# relais-with-led-indicator.net
KiCad netlist of a schematic drawn in EAGLE
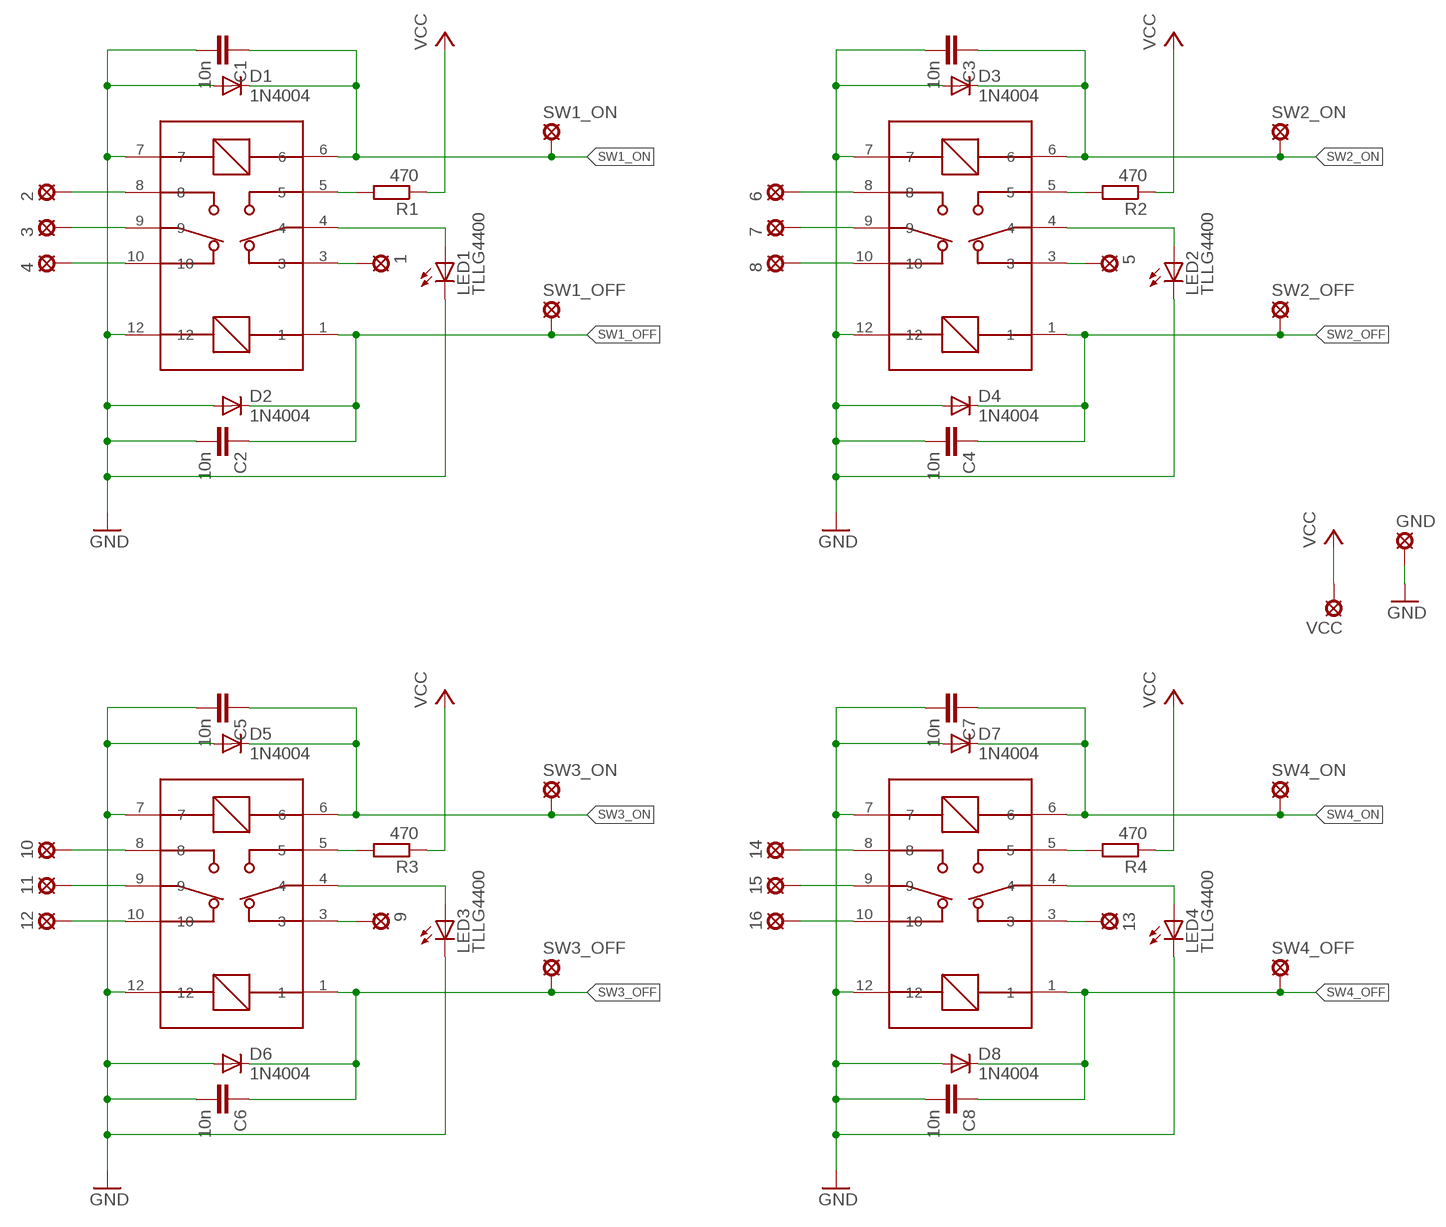
[diagram p0: schematic, sheet 1]

(export (version "E")
  (design (tool "Eeschema 10.0.6"))
  (components
    (comp (ref "1")
      (value "LSP10")
      (footprint "eagle-import:LSP10")
      (libsource (lib "eagle-import") (part "LSP10"))
    )
    (comp (ref "2")
      (value "LSP10")
      (footprint "eagle-import:LSP10")
      (libsource (lib "eagle-import") (part "LSP10"))
    )
    (comp (ref "3")
      (value "LSP10")
      (footprint "eagle-import:LSP10")
      (libsource (lib "eagle-import") (part "LSP10"))
    )
    (comp (ref "4")
      (value "LSP10")
      (footprint "eagle-import:LSP10")
      (libsource (lib "eagle-import") (part "LSP10"))
    )
    (comp (ref "5")
      (value "LSP10")
      (footprint "eagle-import:LSP10")
      (libsource (lib "eagle-import") (part "LSP10"))
    )
    (comp (ref "6")
      (value "LSP10")
      (footprint "eagle-import:LSP10")
      (libsource (lib "eagle-import") (part "LSP10"))
    )
    (comp (ref "7")
      (value "LSP10")
      (footprint "eagle-import:LSP10")
      (libsource (lib "eagle-import") (part "LSP10"))
    )
    (comp (ref "8")
      (value "LSP10")
      (footprint "eagle-import:LSP10")
      (libsource (lib "eagle-import") (part "LSP10"))
    )
    (comp (ref "9")
      (value "LSP10")
      (footprint "eagle-import:LSP10")
      (libsource (lib "eagle-import") (part "LSP10"))
    )
    (comp (ref "10")
      (value "LSP10")
      (footprint "eagle-import:LSP10")
      (libsource (lib "eagle-import") (part "LSP10"))
    )
    (comp (ref "11")
      (value "LSP10")
      (footprint "eagle-import:LSP10")
      (libsource (lib "eagle-import") (part "LSP10"))
    )
    (comp (ref "12")
      (value "LSP10")
      (footprint "eagle-import:LSP10")
      (libsource (lib "eagle-import") (part "LSP10"))
    )
    (comp (ref "13")
      (value "LSP10")
      (footprint "eagle-import:LSP10")
      (libsource (lib "eagle-import") (part "LSP10"))
    )
    (comp (ref "14")
      (value "LSP10")
      (footprint "eagle-import:LSP10")
      (libsource (lib "eagle-import") (part "LSP10"))
    )
    (comp (ref "15")
      (value "LSP10")
      (footprint "eagle-import:LSP10")
      (libsource (lib "eagle-import") (part "LSP10"))
    )
    (comp (ref "16")
      (value "LSP10")
      (footprint "eagle-import:LSP10")
      (libsource (lib "eagle-import") (part "LSP10"))
    )
    (comp (ref "C1")
      (value "10n")
      (footprint "eagle-import:C050-024X044")
      (libsource (lib "eagle-import") (part "C-EU050-024X044"))
    )
    (comp (ref "C2")
      (value "10n")
      (footprint "eagle-import:C050-024X044")
      (libsource (lib "eagle-import") (part "C-EU050-024X044"))
    )
    (comp (ref "C3")
      (value "10n")
      (footprint "eagle-import:C050-024X044")
      (libsource (lib "eagle-import") (part "C-EU050-024X044"))
    )
    (comp (ref "C4")
      (value "10n")
      (footprint "eagle-import:C050-024X044")
      (libsource (lib "eagle-import") (part "C-EU050-024X044"))
    )
    (comp (ref "C5")
      (value "10n")
      (footprint "eagle-import:C050-024X044")
      (libsource (lib "eagle-import") (part "C-EU050-024X044"))
    )
    (comp (ref "C6")
      (value "10n")
      (footprint "eagle-import:C050-024X044")
      (libsource (lib "eagle-import") (part "C-EU050-024X044"))
    )
    (comp (ref "C7")
      (value "10n")
      (footprint "eagle-import:C050-024X044")
      (libsource (lib "eagle-import") (part "C-EU050-024X044"))
    )
    (comp (ref "C8")
      (value "10n")
      (footprint "eagle-import:C050-024X044")
      (libsource (lib "eagle-import") (part "C-EU050-024X044"))
    )
    (comp (ref "D1")
      (value "1N4004")
      (footprint "eagle-import:DO41-10")
      (libsource (lib "eagle-import") (part "1N4004"))
    )
    (comp (ref "D2")
      (value "1N4004")
      (footprint "eagle-import:DO41-10")
      (libsource (lib "eagle-import") (part "1N4004"))
    )
    (comp (ref "D3")
      (value "1N4004")
      (footprint "eagle-import:DO41-10")
      (libsource (lib "eagle-import") (part "1N4004"))
    )
    (comp (ref "D4")
      (value "1N4004")
      (footprint "eagle-import:DO41-10")
      (libsource (lib "eagle-import") (part "1N4004"))
    )
    (comp (ref "D5")
      (value "1N4004")
      (footprint "eagle-import:DO41-10")
      (libsource (lib "eagle-import") (part "1N4004"))
    )
    (comp (ref "D6")
      (value "1N4004")
      (footprint "eagle-import:DO41-10")
      (libsource (lib "eagle-import") (part "1N4004"))
    )
    (comp (ref "D7")
      (value "1N4004")
      (footprint "eagle-import:DO41-10")
      (libsource (lib "eagle-import") (part "1N4004"))
    )
    (comp (ref "D8")
      (value "1N4004")
      (footprint "eagle-import:DO41-10")
      (libsource (lib "eagle-import") (part "1N4004"))
    )
    (comp (ref "GND")
      (value "LSP10")
      (footprint "eagle-import:LSP10")
      (libsource (lib "eagle-import") (part "LSP10"))
    )
    (comp (ref "LED1")
      (value "TLLG4400")
      (footprint "eagle-import:LED3MM")
      (fields (field (name "MF") "VISHAY SEMICONDUCTOR"))
      (libsource (lib "eagle-import") (part "TLLG4400"))
    )
    (comp (ref "LED2")
      (value "TLLG4400")
      (footprint "eagle-import:LED3MM")
      (fields (field (name "MF") "VISHAY SEMICONDUCTOR"))
      (libsource (lib "eagle-import") (part "TLLG4400"))
    )
    (comp (ref "LED3")
      (value "TLLG4400")
      (footprint "eagle-import:LED3MM")
      (fields (field (name "MF") "VISHAY SEMICONDUCTOR"))
      (libsource (lib "eagle-import") (part "TLLG4400"))
    )
    (comp (ref "LED4")
      (value "TLLG4400")
      (footprint "eagle-import:LED3MM")
      (fields (field (name "MF") "VISHAY SEMICONDUCTOR"))
      (libsource (lib "eagle-import") (part "TLLG4400"))
    )
    (comp (ref "R1")
      (value "470")
      (footprint "eagle-import:0204_7")
      (libsource (lib "eagle-import") (part "R0204/7"))
    )
    (comp (ref "R2")
      (value "470")
      (footprint "eagle-import:0204_7")
      (libsource (lib "eagle-import") (part "R0204/7"))
    )
    (comp (ref "R3")
      (value "470")
      (footprint "eagle-import:0204_7")
      (libsource (lib "eagle-import") (part "R0204/7"))
    )
    (comp (ref "R4")
      (value "470")
      (footprint "eagle-import:0204_7")
      (libsource (lib "eagle-import") (part "R0204/7"))
    )
    (comp (ref "RL1")
      (value "BISTABIL-2-COILS")
      (footprint "eagle-import:BISTABILE-2-COILS")
      (libsource (lib "eagle-import") (part "BISTABIL-2-COILS"))
    )
    (comp (ref "RL2")
      (value "BISTABIL-2-COILS")
      (footprint "eagle-import:BISTABILE-2-COILS")
      (libsource (lib "eagle-import") (part "BISTABIL-2-COILS"))
    )
    (comp (ref "RL3")
      (value "BISTABIL-2-COILS")
      (footprint "eagle-import:BISTABILE-2-COILS")
      (libsource (lib "eagle-import") (part "BISTABIL-2-COILS"))
    )
    (comp (ref "RL4")
      (value "BISTABIL-2-COILS")
      (footprint "eagle-import:BISTABILE-2-COILS")
      (libsource (lib "eagle-import") (part "BISTABIL-2-COILS"))
    )
    (comp (ref "SW1_OFF")
      (value "LSP10")
      (footprint "eagle-import:LSP10")
      (libsource (lib "eagle-import") (part "LSP10"))
    )
    (comp (ref "SW1_ON")
      (value "LSP10")
      (footprint "eagle-import:LSP10")
      (libsource (lib "eagle-import") (part "LSP10"))
    )
    (comp (ref "SW2_OFF")
      (value "LSP10")
      (footprint "eagle-import:LSP10")
      (libsource (lib "eagle-import") (part "LSP10"))
    )
    (comp (ref "SW2_ON")
      (value "LSP10")
      (footprint "eagle-import:LSP10")
      (libsource (lib "eagle-import") (part "LSP10"))
    )
    (comp (ref "SW3_OFF")
      (value "LSP10")
      (footprint "eagle-import:LSP10")
      (libsource (lib "eagle-import") (part "LSP10"))
    )
    (comp (ref "SW3_ON")
      (value "LSP10")
      (footprint "eagle-import:LSP10")
      (libsource (lib "eagle-import") (part "LSP10"))
    )
    (comp (ref "SW4_OFF")
      (value "LSP10")
      (footprint "eagle-import:LSP10")
      (libsource (lib "eagle-import") (part "LSP10"))
    )
    (comp (ref "SW4_ON")
      (value "LSP10")
      (footprint "eagle-import:LSP10")
      (libsource (lib "eagle-import") (part "LSP10"))
    )
    (comp (ref "VCC")
      (value "LSP10")
      (footprint "eagle-import:LSP10")
      (libsource (lib "eagle-import") (part "LSP10"))
    )
  )
  (nets
    (net (code "1") (name "GND") (class "Default")
      (node (ref "C1") (pin "2") (pinfunction "2_2") (pintype "passive"))
      (node (ref "C2") (pin "2") (pinfunction "2_2") (pintype "passive"))
      (node (ref "C3") (pin "2") (pinfunction "2_2") (pintype "passive"))
      (node (ref "C4") (pin "2") (pinfunction "2_2") (pintype "passive"))
      (node (ref "C5") (pin "2") (pinfunction "2_2") (pintype "passive"))
      (node (ref "C6") (pin "2") (pinfunction "2_2") (pintype "passive"))
      (node (ref "C7") (pin "2") (pinfunction "2_2") (pintype "passive"))
      (node (ref "C8") (pin "2") (pinfunction "2_2") (pintype "passive"))
      (node (ref "D1") (pin "A") (pinfunction "A_A") (pintype "passive"))
      (node (ref "D2") (pin "A") (pinfunction "A_A") (pintype "passive"))
      (node (ref "D3") (pin "A") (pinfunction "A_A") (pintype "passive"))
      (node (ref "D4") (pin "A") (pinfunction "A_A") (pintype "passive"))
      (node (ref "D5") (pin "A") (pinfunction "A_A") (pintype "passive"))
      (node (ref "D6") (pin "A") (pinfunction "A_A") (pintype "passive"))
      (node (ref "D7") (pin "A") (pinfunction "A_A") (pintype "passive"))
      (node (ref "D8") (pin "A") (pinfunction "A_A") (pintype "passive"))
      (node (ref "GND") (pin "MP") (pinfunction "MP_MP") (pintype "passive"))
      (node (ref "LED1") (pin "K") (pinfunction "C_K") (pintype "passive"))
      (node (ref "LED2") (pin "K") (pinfunction "C_K") (pintype "passive"))
      (node (ref "LED3") (pin "K") (pinfunction "C_K") (pintype "passive"))
      (node (ref "LED4") (pin "K") (pinfunction "C_K") (pintype "passive"))
      (node (ref "RL1") (pin "12") (pinfunction "12_12") (pintype "bidirectional"))
      (node (ref "RL1") (pin "7") (pinfunction "7_7") (pintype "bidirectional"))
      (node (ref "RL2") (pin "12") (pinfunction "12_12") (pintype "bidirectional"))
      (node (ref "RL2") (pin "7") (pinfunction "7_7") (pintype "bidirectional"))
      (node (ref "RL3") (pin "12") (pinfunction "12_12") (pintype "bidirectional"))
      (node (ref "RL3") (pin "7") (pinfunction "7_7") (pintype "bidirectional"))
      (node (ref "RL4") (pin "12") (pinfunction "12_12") (pintype "bidirectional"))
      (node (ref "RL4") (pin "7") (pinfunction "7_7") (pintype "bidirectional"))
    )
    (net (code "2") (name "Net-(1-PadMP)") (class "Default")
      (node (ref "1") (pin "MP") (pinfunction "MP_MP") (pintype "passive"))
      (node (ref "RL1") (pin "3") (pinfunction "3_3") (pintype "bidirectional"))
    )
    (net (code "3") (name "Net-(2-PadMP)") (class "Default")
      (node (ref "2") (pin "MP") (pinfunction "MP_MP") (pintype "passive"))
      (node (ref "RL1") (pin "8") (pinfunction "8_8") (pintype "bidirectional"))
    )
    (net (code "4") (name "Net-(3-PadMP)") (class "Default")
      (node (ref "3") (pin "MP") (pinfunction "MP_MP") (pintype "passive"))
      (node (ref "RL1") (pin "9") (pinfunction "9_9") (pintype "bidirectional"))
    )
    (net (code "5") (name "Net-(4-PadMP)") (class "Default")
      (node (ref "4") (pin "MP") (pinfunction "MP_MP") (pintype "passive"))
      (node (ref "RL1") (pin "10") (pinfunction "10_10") (pintype "bidirectional"))
    )
    (net (code "6") (name "Net-(5-PadMP)") (class "Default")
      (node (ref "5") (pin "MP") (pinfunction "MP_MP") (pintype "passive"))
      (node (ref "RL2") (pin "3") (pinfunction "3_3") (pintype "bidirectional"))
    )
    (net (code "7") (name "Net-(6-PadMP)") (class "Default")
      (node (ref "6") (pin "MP") (pinfunction "MP_MP") (pintype "passive"))
      (node (ref "RL2") (pin "8") (pinfunction "8_8") (pintype "bidirectional"))
    )
    (net (code "8") (name "Net-(7-PadMP)") (class "Default")
      (node (ref "7") (pin "MP") (pinfunction "MP_MP") (pintype "passive"))
      (node (ref "RL2") (pin "9") (pinfunction "9_9") (pintype "bidirectional"))
    )
    (net (code "9") (name "Net-(8-PadMP)") (class "Default")
      (node (ref "8") (pin "MP") (pinfunction "MP_MP") (pintype "passive"))
      (node (ref "RL2") (pin "10") (pinfunction "10_10") (pintype "bidirectional"))
    )
    (net (code "10") (name "Net-(9-PadMP)") (class "Default")
      (node (ref "9") (pin "MP") (pinfunction "MP_MP") (pintype "passive"))
      (node (ref "RL3") (pin "3") (pinfunction "3_3") (pintype "bidirectional"))
    )
    (net (code "11") (name "Net-(10-PadMP)") (class "Default")
      (node (ref "10") (pin "MP") (pinfunction "MP_MP") (pintype "passive"))
      (node (ref "RL3") (pin "8") (pinfunction "8_8") (pintype "bidirectional"))
    )
    (net (code "12") (name "Net-(11-PadMP)") (class "Default")
      (node (ref "11") (pin "MP") (pinfunction "MP_MP") (pintype "passive"))
      (node (ref "RL3") (pin "9") (pinfunction "9_9") (pintype "bidirectional"))
    )
    (net (code "13") (name "Net-(12-PadMP)") (class "Default")
      (node (ref "12") (pin "MP") (pinfunction "MP_MP") (pintype "passive"))
      (node (ref "RL3") (pin "10") (pinfunction "10_10") (pintype "bidirectional"))
    )
    (net (code "14") (name "Net-(13-PadMP)") (class "Default")
      (node (ref "13") (pin "MP") (pinfunction "MP_MP") (pintype "passive"))
      (node (ref "RL4") (pin "3") (pinfunction "3_3") (pintype "bidirectional"))
    )
    (net (code "15") (name "Net-(14-PadMP)") (class "Default")
      (node (ref "14") (pin "MP") (pinfunction "MP_MP") (pintype "passive"))
      (node (ref "RL4") (pin "8") (pinfunction "8_8") (pintype "bidirectional"))
    )
    (net (code "16") (name "Net-(15-PadMP)") (class "Default")
      (node (ref "15") (pin "MP") (pinfunction "MP_MP") (pintype "passive"))
      (node (ref "RL4") (pin "9") (pinfunction "9_9") (pintype "bidirectional"))
    )
    (net (code "17") (name "Net-(16-PadMP)") (class "Default")
      (node (ref "16") (pin "MP") (pinfunction "MP_MP") (pintype "passive"))
      (node (ref "RL4") (pin "10") (pinfunction "10_10") (pintype "bidirectional"))
    )
    (net (code "18") (name "Net-(LED1-PadA)") (class "Default")
      (node (ref "LED1") (pin "A") (pinfunction "A_A") (pintype "passive"))
      (node (ref "RL1") (pin "4") (pinfunction "4_4") (pintype "bidirectional"))
    )
    (net (code "19") (name "Net-(LED2-PadA)") (class "Default")
      (node (ref "LED2") (pin "A") (pinfunction "A_A") (pintype "passive"))
      (node (ref "RL2") (pin "4") (pinfunction "4_4") (pintype "bidirectional"))
    )
    (net (code "20") (name "Net-(LED3-PadA)") (class "Default")
      (node (ref "LED3") (pin "A") (pinfunction "A_A") (pintype "passive"))
      (node (ref "RL3") (pin "4") (pinfunction "4_4") (pintype "bidirectional"))
    )
    (net (code "21") (name "Net-(LED4-PadA)") (class "Default")
      (node (ref "LED4") (pin "A") (pinfunction "A_A") (pintype "passive"))
      (node (ref "RL4") (pin "4") (pinfunction "4_4") (pintype "bidirectional"))
    )
    (net (code "22") (name "Net-(R1-Pad2)") (class "Default")
      (node (ref "R1") (pin "2") (pinfunction "2_2") (pintype "passive"))
      (node (ref "RL1") (pin "5") (pinfunction "5_5") (pintype "bidirectional"))
    )
    (net (code "23") (name "Net-(R2-Pad2)") (class "Default")
      (node (ref "R2") (pin "2") (pinfunction "2_2") (pintype "passive"))
      (node (ref "RL2") (pin "5") (pinfunction "5_5") (pintype "bidirectional"))
    )
    (net (code "24") (name "Net-(R3-Pad2)") (class "Default")
      (node (ref "R3") (pin "2") (pinfunction "2_2") (pintype "passive"))
      (node (ref "RL3") (pin "5") (pinfunction "5_5") (pintype "bidirectional"))
    )
    (net (code "25") (name "Net-(R4-Pad2)") (class "Default")
      (node (ref "R4") (pin "2") (pinfunction "2_2") (pintype "passive"))
      (node (ref "RL4") (pin "5") (pinfunction "5_5") (pintype "bidirectional"))
    )
    (net (code "26") (name "SW1_OFF") (class "Default")
      (node (ref "C2") (pin "1") (pinfunction "1_1") (pintype "passive"))
      (node (ref "D2") (pin "C") (pinfunction "C_C") (pintype "passive"))
      (node (ref "RL1") (pin "1") (pinfunction "1_1") (pintype "bidirectional"))
      (node (ref "SW1_OFF") (pin "MP") (pinfunction "MP_MP") (pintype "passive"))
    )
    (net (code "27") (name "SW1_ON") (class "Default")
      (node (ref "C1") (pin "1") (pinfunction "1_1") (pintype "passive"))
      (node (ref "D1") (pin "C") (pinfunction "C_C") (pintype "passive"))
      (node (ref "RL1") (pin "6") (pinfunction "6_6") (pintype "bidirectional"))
      (node (ref "SW1_ON") (pin "MP") (pinfunction "MP_MP") (pintype "passive"))
    )
    (net (code "28") (name "SW2_OFF") (class "Default")
      (node (ref "C4") (pin "1") (pinfunction "1_1") (pintype "passive"))
      (node (ref "D4") (pin "C") (pinfunction "C_C") (pintype "passive"))
      (node (ref "RL2") (pin "1") (pinfunction "1_1") (pintype "bidirectional"))
      (node (ref "SW2_OFF") (pin "MP") (pinfunction "MP_MP") (pintype "passive"))
    )
    (net (code "29") (name "SW2_ON") (class "Default")
      (node (ref "C3") (pin "1") (pinfunction "1_1") (pintype "passive"))
      (node (ref "D3") (pin "C") (pinfunction "C_C") (pintype "passive"))
      (node (ref "RL2") (pin "6") (pinfunction "6_6") (pintype "bidirectional"))
      (node (ref "SW2_ON") (pin "MP") (pinfunction "MP_MP") (pintype "passive"))
    )
    (net (code "30") (name "SW3_OFF") (class "Default")
      (node (ref "C6") (pin "1") (pinfunction "1_1") (pintype "passive"))
      (node (ref "D6") (pin "C") (pinfunction "C_C") (pintype "passive"))
      (node (ref "RL3") (pin "1") (pinfunction "1_1") (pintype "bidirectional"))
      (node (ref "SW3_OFF") (pin "MP") (pinfunction "MP_MP") (pintype "passive"))
    )
    (net (code "31") (name "SW3_ON") (class "Default")
      (node (ref "C5") (pin "1") (pinfunction "1_1") (pintype "passive"))
      (node (ref "D5") (pin "C") (pinfunction "C_C") (pintype "passive"))
      (node (ref "RL3") (pin "6") (pinfunction "6_6") (pintype "bidirectional"))
      (node (ref "SW3_ON") (pin "MP") (pinfunction "MP_MP") (pintype "passive"))
    )
    (net (code "32") (name "SW4_OFF") (class "Default")
      (node (ref "C8") (pin "1") (pinfunction "1_1") (pintype "passive"))
      (node (ref "D8") (pin "C") (pinfunction "C_C") (pintype "passive"))
      (node (ref "RL4") (pin "1") (pinfunction "1_1") (pintype "bidirectional"))
      (node (ref "SW4_OFF") (pin "MP") (pinfunction "MP_MP") (pintype "passive"))
    )
    (net (code "33") (name "SW4_ON") (class "Default")
      (node (ref "C7") (pin "1") (pinfunction "1_1") (pintype "passive"))
      (node (ref "D7") (pin "C") (pinfunction "C_C") (pintype "passive"))
      (node (ref "RL4") (pin "6") (pinfunction "6_6") (pintype "bidirectional"))
      (node (ref "SW4_ON") (pin "MP") (pinfunction "MP_MP") (pintype "passive"))
    )
    (net (code "34") (name "VCC") (class "Default")
      (node (ref "R1") (pin "1") (pinfunction "1_1") (pintype "passive"))
      (node (ref "R2") (pin "1") (pinfunction "1_1") (pintype "passive"))
      (node (ref "R3") (pin "1") (pinfunction "1_1") (pintype "passive"))
      (node (ref "R4") (pin "1") (pinfunction "1_1") (pintype "passive"))
      (node (ref "VCC") (pin "MP") (pinfunction "MP_MP") (pintype "passive"))
    )
  )
)
